# SCH-00001-AB-01.net
KiCad netlist of a schematic drawn in Altium Designer
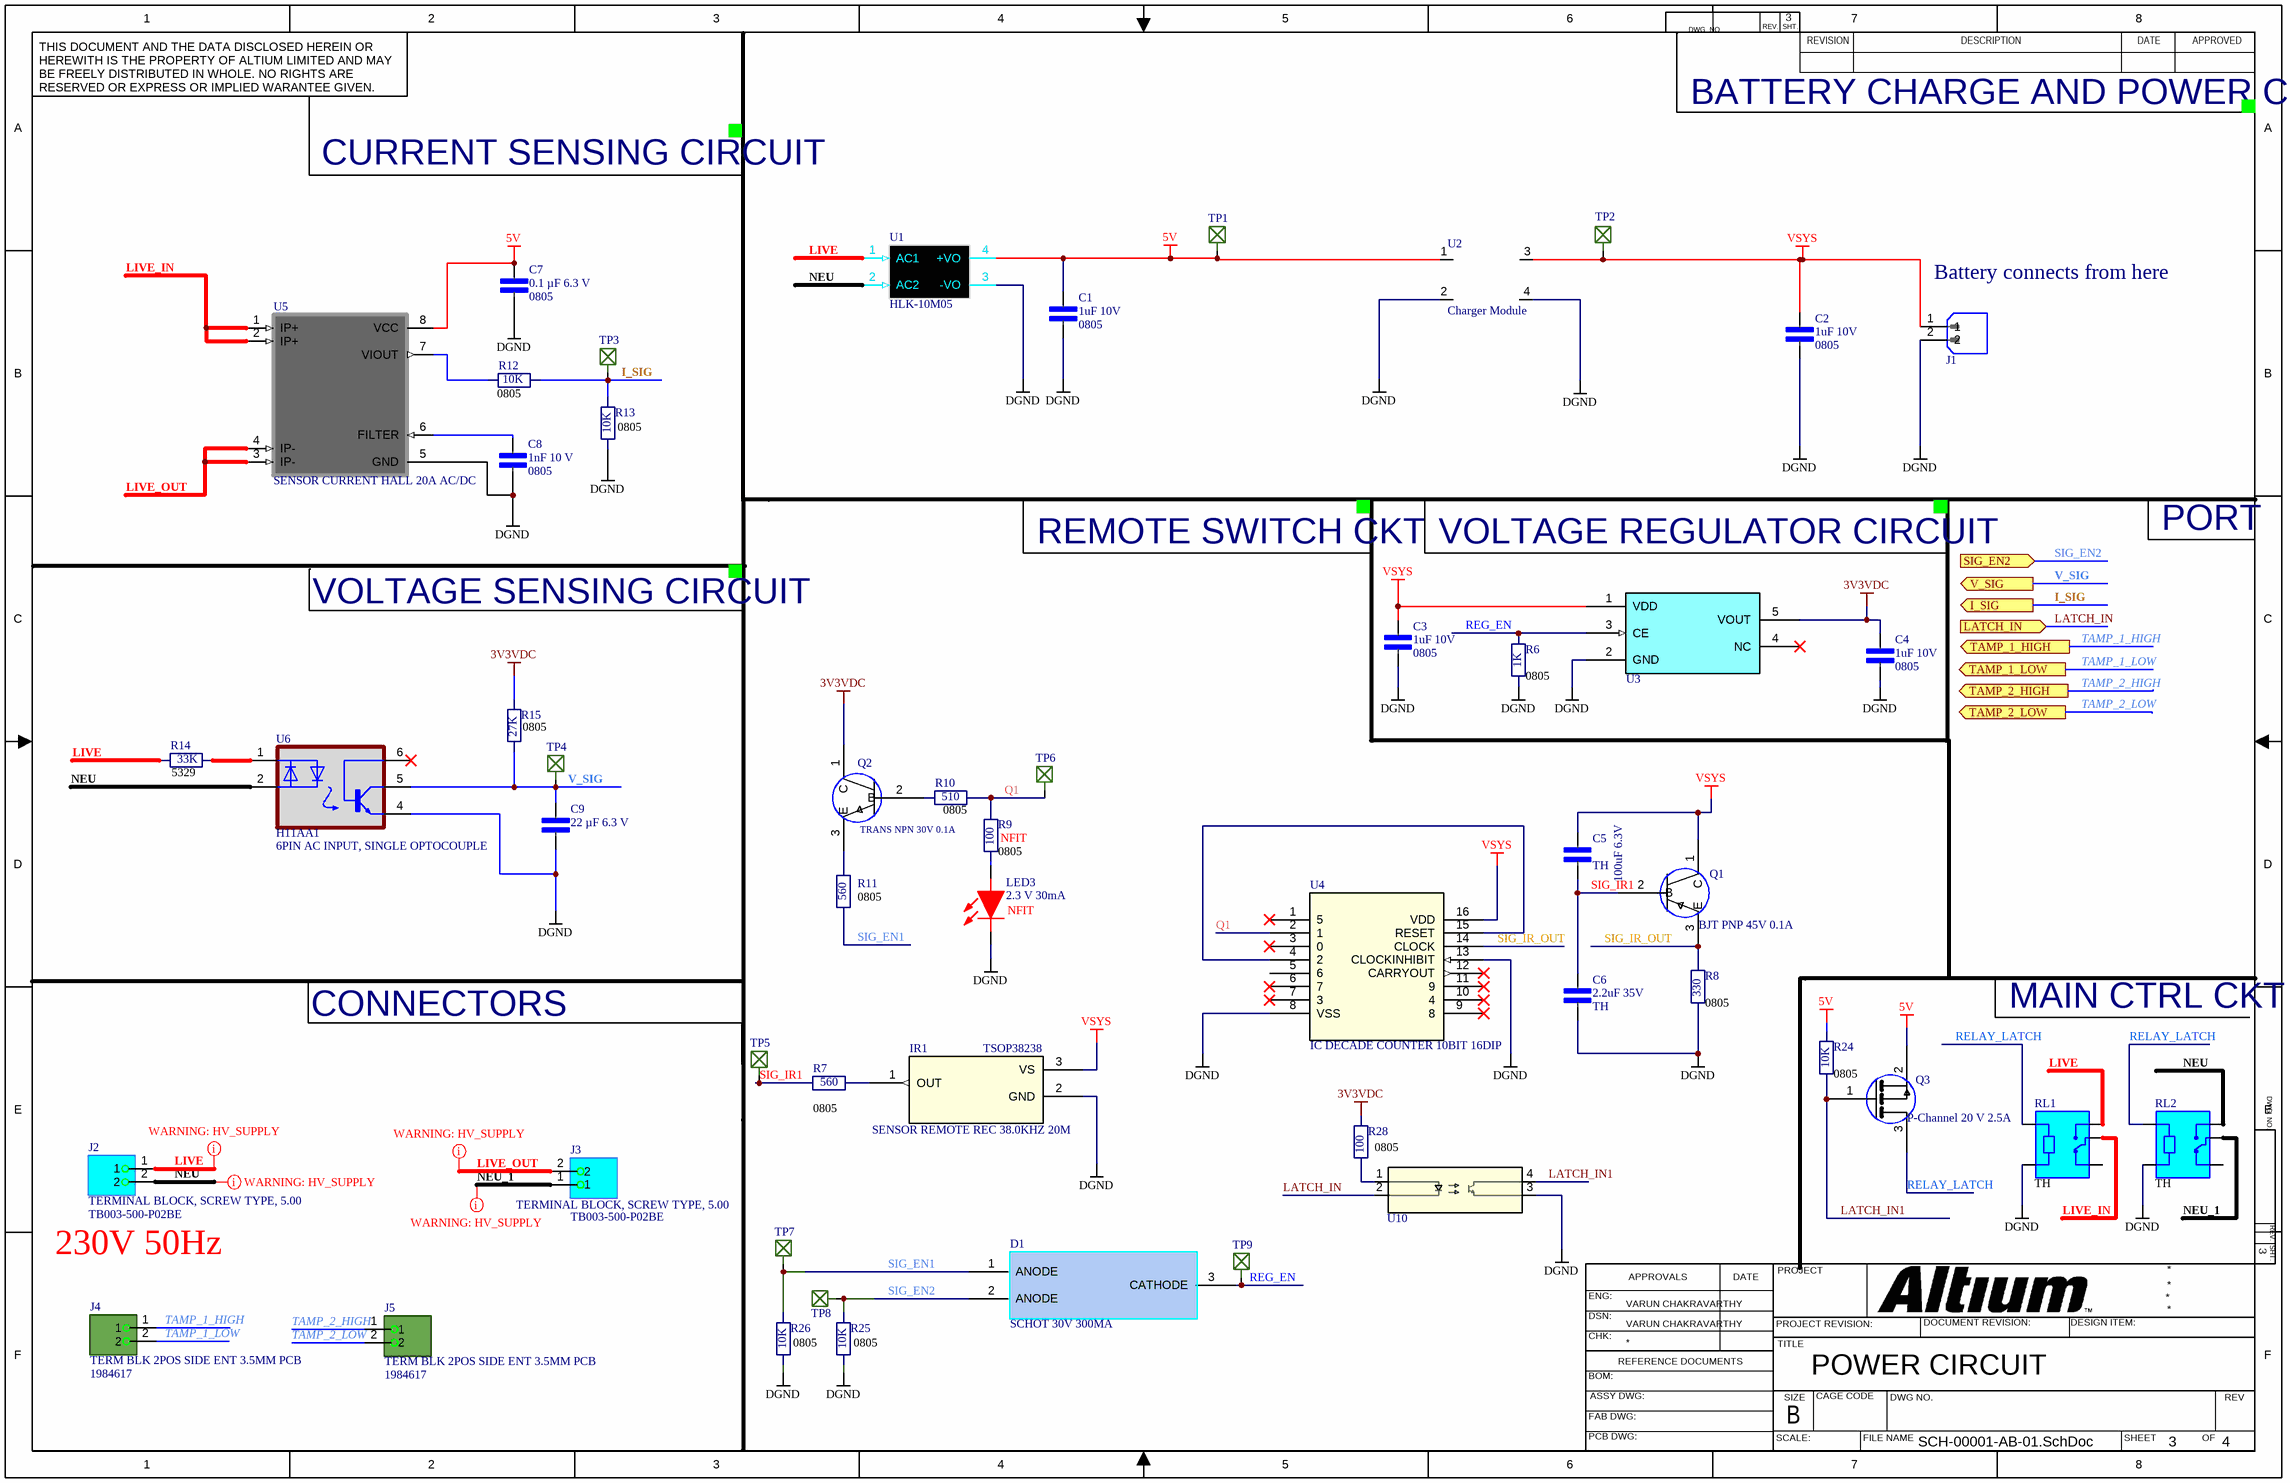
[diagram p0: SCH-00001-AB-01.SchDoc]

(export (version "E")
  (design (tool "Eeschema 10.0.6"))
  (components
    (comp (ref "C1")
      (value "1uF 10V")
      (footprint "CAP0805")
      (description "1 µF ±10% 10V Ceramic Capacitor X7R 0805 (2012 Metric)")
      (fields
        (field (name "MANUFACTURER") "Murata Electronics")
        (field (name "MANUFACTURER PART NO.") "GRM21BR71A105KA01L")
        (field (name "PACKAGE") "0805")
        (field (name "DATE DRAWN") "01/09/24")
        (field (name "DRAWN BY") "Varun Chakravarthy")
      )
      (libsource (lib "00001-A-01") (part "GRM21BR71A105KA01L"))
    )
    (comp (ref "C2")
      (value "1uF 10V")
      (footprint "CAP0805")
      (description "1 µF ±10% 10V Ceramic Capacitor X7R 0805 (2012 Metric)")
      (fields
        (field (name "MANUFACTURER") "Murata Electronics")
        (field (name "MANUFACTURER PART NO.") "GRM21BR71A105KA01L")
        (field (name "PACKAGE") "0805")
        (field (name "DATE DRAWN") "01/09/24")
        (field (name "DRAWN BY") "Varun Chakravarthy")
      )
      (libsource (lib "00001-A-01") (part "GRM21BR71A105KA01L"))
    )
    (comp (ref "C3")
      (value "1uF 10V")
      (footprint "CAP0805")
      (description "1 µF ±10% 10V Ceramic Capacitor X7R 0805 (2012 Metric)")
      (fields
        (field (name "MANUFACTURER") "Murata Electronics")
        (field (name "MANUFACTURER PART NO.") "GRM21BR71A105KA01L")
        (field (name "PACKAGE") "0805")
        (field (name "DATE DRAWN") "01/09/24")
        (field (name "DRAWN BY") "Varun Chakravarthy")
      )
      (libsource (lib "00001-A-01") (part "GRM21BR71A105KA01L"))
    )
    (comp (ref "C4")
      (value "1uF 10V")
      (footprint "CAP0805")
      (description "1 µF ±10% 10V Ceramic Capacitor X7R 0805 (2012 Metric)")
      (fields
        (field (name "MANUFACTURER") "Murata Electronics")
        (field (name "MANUFACTURER PART NO.") "GRM21BR71A105KA01L")
        (field (name "PACKAGE") "0805")
        (field (name "DATE DRAWN") "01/09/24")
        (field (name "DRAWN BY") "Varun Chakravarthy")
      )
      (libsource (lib "00001-A-01") (part "GRM21BR71A105KA01L"))
    )
    (comp (ref "C5")
      (value "100uF 6.3V")
      (footprint "EC-A_PAN")
      (description "100 µF 6.3 V Aluminum Electrolytic Capacitors Radial, Can 2000 Hrs @ 85°C")
      (fields
        (field (name "MANUFACTURER") "Panasonic Electronic Components")
        (field (name "MANUFACTURER PART NO.") "ECA-0JM101")
        (field (name "VALUE 2") "TH")
        (field (name "DATE DRAWN") "12/09/2024")
        (field (name "DRAWN BY") "Varun Chakravarthy")
      )
      (libsource (lib "00001-A-01") (part "ECA-0JM101"))
    )
    (comp (ref "C6")
      (value "2.2uF 35V")
      (footprint "CAP_RN_10X12P5_NCH")
      (description "2.2 µF 35 V Aluminum Electrolytic Capacitors Radial, Can 20000 Hrs @ 105°C")
      (fields
        (field (name "MANUFACTURER") "Nichicon")
        (field (name "MANUFACTURER PART NO.") "UPX1V2R2MPD")
        (field (name "VALUE 2") "TH")
        (field (name "DATE DRAWN") "12/09/2024")
        (field (name "DRAWN BY") "Varun Chakravarthy")
      )
      (libsource (lib "00001-A-01") (part "UPX1V2R2MPD"))
    )
    (comp (ref "C7")
      (value "0.1 µF 6.3 V")
      (footprint "CAP0805")
      (description "0.1 µF ±10% 6.3V Ceramic Capacitor X5R 0805 (2012 Metric)")
      (fields
        (field (name "MANUFACTURER") "KYOCERA AVX")
        (field (name "MANUFACTURER PART NO.") "08056D104KAT2A")
        (field (name "VALUE 2") "0805")
        (field (name "DATE DRAWN") "04/07/24")
        (field (name "DRAWN BY") "Varun Chakravarthy")
      )
      (libsource (lib "00001-A-01") (part "08056D104KAT2A"))
    )
    (comp (ref "C8")
      (value "1nF 10 V")
      (footprint "CAP0805")
      (description "1000 pF ±10% 10V Ceramic Capacitor X7R 0805 (2012 Metric)")
      (fields
        (field (name "MANUFACTURER") "KEMET")
        (field (name "MANUFACTURER PART NO.") "C0805C102K8RAC7800")
        (field (name "VALUE 2") "0805")
        (field (name "DATE DRAWN") "16/09/24")
        (field (name "DRAWN BY") "Varun Chakravarthy")
      )
      (libsource (lib "00001-A-01") (part "C0805C102K8RAC7800"))
    )
    (comp (ref "C9")
      (value "22 µF 6.3 V")
      (footprint "CAP0805")
      (description "22 µF ±10% 6.3V Ceramic Capacitor X5R 0805 (2012 Metric)")
      (fields
        (field (name "MANUFACTURER") "Samsung Electro-Mechanics")
        (field (name "MANUFACTURER PART NO.") "CL21A226KQCLRNC")
        (field (name "DATE DRAWN") "03/9/2024")
        (field (name "DRAWN BY") "Varun Chakravarthy")
      )
      (libsource (lib "00001-A-01") (part "CL21A226KQCLRNC"))
    )
    (comp (ref "D1")
      (value "SCHOT 30V 300MA")
      (footprint "SOT-323_2P2X1P35X1P3_STM-M")
      (description "Remote Receiver Sensor 38.0kHz 20m Through Hole")
      (fields
        (field (name "MANUFACTURER") "STMicroelectronics")
        (field (name "MANUFACTURER PART NO.") "BAT30CWFILM")
        (field (name "DATE DRAWN") "12/07/24")
        (field (name "DRAWN BY") "Varun Chakravarthy")
      )
      (libsource (lib "00001-A-01") (part "BAT30CWFILM"))
    )
    (comp (ref "IR1")
      (value "TSOP38238")
      (footprint "TSOP382")
      (description "Remote Receiver Sensor 38.0kHz 20m Through Hole")
      (fields
        (field (name "MANUFACTURER") "KYOCERA AVX")
        (field (name "DISTRIBUTOR 1 PART NO.") "751-1227-ND")
        (field (name "ALTIUM_VALUE") "SENSOR REMOTE REC 38.0KHZ 20M")
        (field (name "DATE DRAWN") "04/07/24")
        (field (name "DRAWN BY") "Varun Chakravarthy")
      )
      (libsource (lib "00001-A-01") (part "TSOP38238"))
    )
    (comp (ref "J1")
      (value "1053131102")
      (footprint "CON_1053131102")
      (description "Connector Header Through Hole, Right Angle 2 position 0.049\" (1.25mm)")
      (fields
        (field (name "MANUFACTURER") "Molex")
        (field (name "DISTRIBUTOR 1 PART NO.") "WM16893-ND")
        (field (name "DATE DRAWN") "6/10/24")
        (field (name "DRAWN BY") "Varun")
        (field (name "VERIFIED BY") "*")
      )
      (libsource (lib "00001-A-01") (part "1053131102"))
    )
    (comp (ref "J2")
      (value "TERMINAL BLOCK, SCREW TYPE, 5.00")
      (footprint "CUI_TB003-500-P02BE")
      (description "2 Position Wire to Board Terminal Block Horizontal with Board 0.197\" (5.00mm) Through Hole")
      (fields
        (field (name "MANUFACTURER") "Same Sky")
        (field (name "DISTRIBUTOR 1 PART NO.") "102-6161-ND")
        (field (name "MANUFACTURER PART NO.") "TB003-500-P02BE")
        (field (name "DATE DRAWN") "26/09/24")
        (field (name "DRAWN BY") "Varun Chakravarthy")
      )
      (libsource (lib "") (part "TB003-500-P02BE_1"))
    )
    (comp (ref "J3")
      (value "TERMINAL BLOCK, SCREW TYPE, 5.00")
      (footprint "CUI_TB003-500-P02BE")
      (description "2 Position Wire to Board Terminal Block Horizontal with Board 0.197\" (5.00mm) Through Hole")
      (fields
        (field (name "MANUFACTURER") "Same Sky")
        (field (name "DISTRIBUTOR 1 PART NO.") "102-6161-ND")
        (field (name "MANUFACTURER PART NO.") "TB003-500-P02BE")
        (field (name "DATE DRAWN") "26/09/24")
        (field (name "DRAWN BY") "Varun Chakravarthy")
      )
      (libsource (lib "00001-A-01") (part "TB003-500-P02BE"))
    )
    (comp (ref "J4")
      (value "TERM BLK 2POS SIDE ENT 3.5MM PCB")
      (footprint "PHOENIX_1984617")
      (description "2 Position Wire to Board Terminal Block Horizontal with Board 0.138\" (3.50mm) Through Hole")
      (fields
        (field (name "MANUFACTURER") "Phoenix Contact")
        (field (name "DISTRIBUTOR 1 PART NO.") "277-1721-ND")
        (field (name "MANUFACTURER PART NO.") "1984617")
        (field (name "DATE DRAWN") "17/09/24")
        (field (name "DRAWN BY") "Varun Chakravarthy")
      )
      (libsource (lib "00001-A-01") (part "1984617"))
    )
    (comp (ref "J5")
      (value "TERM BLK 2POS SIDE ENT 3.5MM PCB")
      (footprint "PHOENIX_1984617")
      (description "2 Position Wire to Board Terminal Block Horizontal with Board 0.138\" (3.50mm) Through Hole")
      (fields
        (field (name "MANUFACTURER") "Phoenix Contact")
        (field (name "DISTRIBUTOR 1 PART NO.") "277-1721-ND")
        (field (name "MANUFACTURER PART NO.") "1984617")
        (field (name "DATE DRAWN") "17/09/24")
        (field (name "DRAWN BY") "Varun Chakravarthy")
      )
      (libsource (lib "") (part "1984617_1"))
    )
    (comp (ref "LED3")
      (value "2.3 V 30mA")
      (footprint "LEDM2214X140N")
      (description "Standard LEDs - SMD Super Red, 633nm 224mcd, 20mA")
      (fields
        (field (name "MANUFACTURER") "ams OSRAM")
        (field (name "DISTRIBUTOR 1 PART NO.") "720-LSM676-Q2S1-1-Z")
        (field (name "FIT/NFIT") "NFIT")
        (field (name "DRAWN BY") "Varun")
        (field (name "DATE DRAWN") "12/072023")
        (field (name "VERIFIED BY") "*")
      )
      (libsource (lib "00001-A-01") (part "LS M676-Q2S1-1-Z"))
    )
    (comp (ref "Q1")
      (value "BJT PNP 45V 0.1A")
      (footprint "TO-92-3L_5P33X5P2_ONS")
      (description "P-Channel 20 V 2.5A (Ta) 800mW (Ta) Surface Mount SOT-23-3")
      (fields
        (field (name "MANUFACTURER") "onsemi")
        (field (name "MANUFACTURER PART NO.") "BC557ATA")
        (field (name "DATE DRAWN") "12/09/24")
        (field (name "DRAWN BY") "Varun Chakravarthy")
      )
      (libsource (lib "00001-A-01") (part "BC557"))
    )
    (comp (ref "Q2")
      (value "TRANS NPN 30V 0.1A")
      (footprint "TO-92-3L_5P33X5P2_ONS")
      (description "Bipolar (BJT) Transistor NPN 30 V 100 mA 300MHz 500 mW Through Hole TO-92-3")
      (fields
        (field (name "MANUFACTURER") "Fairchild Semiconductor")
        (field (name "MANUFACTURER PART NO.") "BC548")
        (field (name "DATE DRAWN") "12/09/24")
        (field (name "DRAWN BY") "Varun Chakravarthy")
      )
      (libsource (lib "00001-A-01") (part "BC548"))
    )
    (comp (ref "Q3")
      (value "P-Channel 20 V 2.5A")
      (footprint "SOT23_DMG2301U_DIO")
      (description "P-Channel 20 V 2.5A (Ta) 800mW (Ta) Surface Mount SOT-23-3")
      (fields
        (field (name "MANUFACTURER") "Diodes Incorporated")
        (field (name "MANUFACTURER PART NO.") "DMG2301U-7")
        (field (name "DATE DRAWN") "05/09/24")
        (field (name "DRAWN BY") "Varun Chakravarthy")
      )
      (libsource (lib "00001-A-01") (part "DMG2301U-7"))
    )
    (comp (ref "R6")
      (value "1K")
      (footprint "RES0805")
      (description "1 kOhms ±5% 0.125W, 1/8W Chip Resistor 0805 (2012 Metric) Automotive AEC-Q200 Thick Film")
      (fields
        (field (name "MANUFACTURER") "Panasonic Electronic Components")
        (field (name "MANUFACTURER PART NO.") "P1.0KACT-ND")
        (field (name "PACKAGE") "0805")
        (field (name "DATE DRAWN") "1/9/2024")
        (field (name "VERIFIED BY") "*")
      )
      (libsource (lib "00001-A-01") (part "ERJ-6GEYJ102V"))
    )
    (comp (ref "R7")
      (value "560")
      (footprint "RES0805")
      (description "560 Ohms ±0.1% 0.125W, 1/8W Chip Resistor 0805 (2012 Metric) Automotive AEC-Q200 Thin Film")
      (fields
        (field (name "MANUFACTURER") "Panasonic Electronic Components")
        (field (name "MANUFACTURER PART NO.") "ERA-6AEB561V")
        (field (name "PACKAGE") "0805")
        (field (name "DATE DRAWN") "12/9/2024")
        (field (name "VERIFIED BY") "*")
      )
      (libsource (lib "00001-A-01") (part "ERA-6AEB561V"))
    )
    (comp (ref "R8")
      (value "330")
      (footprint "RES0805")
      (description "330 Ohms ±0.1% 0.125W, 1/8W Chip Resistor 0805 (2012 Metric) Automotive AEC-Q200 Thin Film")
      (fields
        (field (name "MANUFACTURER") "Panasonic Electronic Components")
        (field (name "MANUFACTURER PART NO.") "ERA-6AEB331V")
        (field (name "PACKAGE") "0805")
        (field (name "DATE DRAWN") "12/9/2024")
        (field (name "VERIFIED BY") "*")
      )
      (libsource (lib "00001-A-01") (part "ERA-6AEB331V"))
    )
    (comp (ref "R9")
      (value "100")
      (footprint "RES0805")
      (description "100 Ohms ±0.1% 0.125W, 1/8W Chip Resistor 0805 (2012 Metric) Automotive AEC-Q200 Thin Film")
      (fields
        (field (name "MANUFACTURER") "Panasonic Electronic Components")
        (field (name "MANUFACTURER PART NO.") "ERA-6AEB101V")
        (field (name "FIT/NFIT") "NFIT")
        (field (name "PACKAGE") "0805")
        (field (name "DATE DRAWN") "12/9/2024")
        (field (name "VERIFIED BY") "*")
      )
      (libsource (lib "00001-A-01") (part "ERA-6AEB101V"))
    )
    (comp (ref "R10")
      (value "510")
      (footprint "RES0805")
      (description "510 Ohms ±0.1% 0.125W, 1/8W Chip Resistor 0805 (2012 Metric) Automotive AEC-Q200 Thin Film")
      (fields
        (field (name "MANUFACTURER") "Panasonic Electronic Components")
        (field (name "MANUFACTURER PART NO.") "ERA-6AEB511V")
        (field (name "PACKAGE") "0805")
        (field (name "DATE DRAWN") "12/9/2024")
        (field (name "VERIFIED BY") "*")
      )
      (libsource (lib "00001-A-01") (part "ERA-6AEB511V"))
    )
    (comp (ref "R11")
      (value "560")
      (footprint "RES0805")
      (description "560 Ohms ±0.1% 0.125W, 1/8W Chip Resistor 0805 (2012 Metric) Automotive AEC-Q200 Thin Film")
      (fields
        (field (name "MANUFACTURER") "Panasonic Electronic Components")
        (field (name "MANUFACTURER PART NO.") "ERA-6AEB561V")
        (field (name "PACKAGE") "0805")
        (field (name "DATE DRAWN") "12/9/2024")
        (field (name "VERIFIED BY") "*")
      )
      (libsource (lib "") (part "ERA-6AEB561V_1"))
    )
    (comp (ref "R12")
      (value "10K")
      (footprint "RES0805")
      (description "10 kOhms ±0.1% 0.125W, 1/8W Chip Resistor 0805 (2012 Metric) Automotive AEC-Q200 Thin Film")
      (fields
        (field (name "MANUFACTURER") "Panasonic Electronic Components")
        (field (name "MANUFACTURER PART NO.") "ERA-6AEB103V")
        (field (name "PACKAGE") "0805")
        (field (name "DATE DRAWN") "1/9/2024")
        (field (name "VERIFIED BY") "*")
      )
      (libsource (lib "") (part "ERA-6AEB103V_1"))
    )
    (comp (ref "R13")
      (value "10K")
      (footprint "RES0805")
      (description "10 kOhms ±0.1% 0.125W, 1/8W Chip Resistor 0805 (2012 Metric) Automotive AEC-Q200 Thin Film")
      (fields
        (field (name "MANUFACTURER") "Panasonic Electronic Components")
        (field (name "MANUFACTURER PART NO.") "ERA-6AEB103V")
        (field (name "PACKAGE") "0805")
        (field (name "DATE DRAWN") "1/9/2024")
        (field (name "VERIFIED BY") "*")
      )
      (libsource (lib "00001-A-01") (part "ERA-6AEB103V"))
    )
    (comp (ref "R14")
      (value "33K")
      (footprint "RES_SMF5_TYCO_TYC")
      (fields
        (field (name "MANUFACTURER") "TE Connectivity Passive Product")
        (field (name "MANUFACTURER PART NO.") "SMF533KJT")
        (field (name "DISTRIBUTOR 1 PART NO.") "A106035CT-ND")
        (field (name "PACKAGE") "5329")
        (field (name "DATE DRAWN") "17/9/2024")
        (field (name "VERIFIED BY") "*")
      )
      (libsource (lib "00001-A-01") (part "SMF533KJT"))
    )
    (comp (ref "R15")
      (value "27K")
      (footprint "RES0805")
      (description "27 kOhms ±5% 0.125W, 1/8W Chip Resistor 0805 (2012 Metric) Automotive AEC-Q200 Thick Film")
      (fields
        (field (name "MANUFACTURER") "Panasonic Electronic Components")
        (field (name "MANUFACTURER PART NO.") "ERJ-6GEYJ273V")
        (field (name "PACKAGE") "0805")
        (field (name "DATE DRAWN") "1/9/2024")
        (field (name "VERIFIED BY") "*")
      )
      (libsource (lib "00001-A-01") (part "ERJ-6GEYJ273V"))
    )
    (comp (ref "R24")
      (value "10K")
      (footprint "RES0805")
      (description "10 kOhms ±0.1% 0.125W, 1/8W Chip Resistor 0805 (2012 Metric) Automotive AEC-Q200 Thin Film")
      (fields
        (field (name "MANUFACTURER") "Panasonic Electronic Components")
        (field (name "MANUFACTURER PART NO.") "ERA-6AEB103V")
        (field (name "PACKAGE") "0805")
        (field (name "DATE DRAWN") "1/9/2024")
        (field (name "VERIFIED BY") "*")
      )
      (libsource (lib "00001-A-01") (part "ERA-6AEB103V"))
    )
    (comp (ref "R25")
      (value "10K")
      (footprint "RES0805")
      (description "10 kOhms ±0.1% 0.125W, 1/8W Chip Resistor 0805 (2012 Metric) Automotive AEC-Q200 Thin Film")
      (fields
        (field (name "MANUFACTURER") "Panasonic Electronic Components")
        (field (name "MANUFACTURER PART NO.") "ERA-6AEB103V")
        (field (name "PACKAGE") "0805")
        (field (name "DATE DRAWN") "1/9/2024")
        (field (name "VERIFIED BY") "*")
      )
      (libsource (lib "00001-A-01") (part "ERA-6AEB103V"))
    )
    (comp (ref "R26")
      (value "10K")
      (footprint "RES0805")
      (description "10 kOhms ±0.1% 0.125W, 1/8W Chip Resistor 0805 (2012 Metric) Automotive AEC-Q200 Thin Film")
      (fields
        (field (name "MANUFACTURER") "Panasonic Electronic Components")
        (field (name "MANUFACTURER PART NO.") "ERA-6AEB103V")
        (field (name "PACKAGE") "0805")
        (field (name "DATE DRAWN") "1/9/2024")
        (field (name "VERIFIED BY") "*")
      )
      (libsource (lib "00001-A-01") (part "ERA-6AEB103V"))
    )
    (comp (ref "R28")
      (value "100")
      (footprint "RES0805")
      (description "100 Ohms ±5% 0.125W, 1/8W Chip Resistor 0805 (2012 Metric) Automotive AEC-Q200 Thick Film")
      (fields
        (field (name "MANUFACTURER") "Panasonic Electronic Components")
        (field (name "MANUFACTURER PART NO.") "ERJ-6GEYJ101V")
        (field (name "PACKAGE") "0805")
        (field (name "DATE DRAWN") "1/9/2024")
        (field (name "VERIFIED BY") "*")
      )
      (libsource (lib "00001-A-01") (part "ERJ-6GEYJ101V"))
    )
    (comp (ref "RL1")
      (value "SRD-05VDC-SL-C")
      (footprint "RELAY_SRD-05VDC-SL-C")
      (description "5V Trigger Relay Module")
      (fields
        (field (name "MANUFACTURER") "SongLe")
        (field (name "DISTRIBUTOR 1 PART NO.") "340142-SRD-05VDC-SL-C")
        (field (name "PACKAGE") "TH")
        (field (name "DATE DRAWN") "12/9/2024")
        (field (name "VERIFIED BY") "*")
      )
      (libsource (lib "00001-A-01") (part "SRD-05VDC-SL-C"))
    )
    (comp (ref "RL2")
      (value "SRD-05VDC-SL-C")
      (footprint "RELAY_SRD-05VDC-SL-C")
      (description "5V Trigger Relay Module")
      (fields
        (field (name "MANUFACTURER") "SongLe")
        (field (name "DISTRIBUTOR 1 PART NO.") "340142-SRD-05VDC-SL-C")
        (field (name "PACKAGE") "TH")
        (field (name "DATE DRAWN") "12/9/2024")
        (field (name "VERIFIED BY") "*")
      )
      (libsource (lib "00001-A-01") (part "SRD-05VDC-SL-C"))
    )
    (comp (ref "TP1")
      (value "TEST point")
      (footprint "TEST_POINT")
      (libsource (lib "00001-A-01") (part "TP"))
    )
    (comp (ref "TP2")
      (value "TEST point")
      (footprint "TEST_POINT")
      (libsource (lib "00001-A-01") (part "TP"))
    )
    (comp (ref "TP3")
      (value "TEST point")
      (footprint "TEST_POINT")
      (libsource (lib "00001-A-01") (part "TP"))
    )
    (comp (ref "TP4")
      (value "TEST point")
      (footprint "TEST_POINT")
      (libsource (lib "00001-A-01") (part "TP"))
    )
    (comp (ref "TP5")
      (value "TEST point")
      (footprint "TEST_POINT")
      (libsource (lib "00001-A-01") (part "TP"))
    )
    (comp (ref "TP6")
      (value "TEST point")
      (footprint "TEST_POINT")
      (libsource (lib "00001-A-01") (part "TP"))
    )
    (comp (ref "TP7")
      (value "TEST point")
      (footprint "TEST_POINT")
      (libsource (lib "00001-A-01") (part "TP"))
    )
    (comp (ref "TP8")
      (value "TEST point")
      (footprint "TEST_POINT")
      (libsource (lib "00001-A-01") (part "TP"))
    )
    (comp (ref "TP9")
      (value "TEST point")
      (footprint "TEST_POINT")
      (libsource (lib "00001-A-01") (part "TP"))
    )
    (comp (ref "U1")
      (value "HLK-10M05")
      (footprint "CONV_HLK-10M05")
      (description "AC to DC Power Supply Module")
      (fields
        (field (name "MANUFACTURER") "Hi-link")
        (field (name "DISTRIBUTOR 1 PART NO.") "EC-4693")
        (field (name "MANUFACTURER PART NO.") "HLK-10M05")
        (field (name "DATE DRAWN") "31/8/24")
        (field (name "DRAWN BY") "Varun")
        (field (name "VERIFIED BY") "*")
      )
      (libsource (lib "00001-A-01") (part "HLK-10M05"))
    )
    (comp (ref "U2")
      (value "Charger Module")
      (footprint "TP5100_MODULE")
      (description "4.2v and 8.4v Dual One/Two Battery Protection Board")
      (fields
        (field (name "MANUFACTURER") "Tap ower ASIC")
        (field (name "MANUFACTURER PART NO.") "TP5100")
        (field (name "DATE DRAWN") "10/07/24")
        (field (name "DRAWN BY") "Varun Chakravarthy")
      )
      (libsource (lib "00001-A-01") (part "TP5100"))
    )
    (comp (ref "U3")
      (value "RP170N331D-TR-FE")
      (footprint "SOT-23-5SC-74A_PE-SOT-23-5-180326_NMD-M")
      (description "Linear Voltage Regulator IC Positive Fixed 1 Output 300mA SOT-23-5")
      (fields
        (field (name "MANUFACTURER") "Nisshinbo Micro Devices Inc.")
        (field (name "DISTRIBUTOR 1 PART NO.") "2129-RP170N331D-TR-FECT-ND")
        (field (name "DATE DRAWN") "31/8/24")
        (field (name "DRAWN BY") "Varun")
        (field (name "VERIFIED BY") "*")
      )
      (libsource (lib "00001-A-01") (part "RP170N331D-TR-FE"))
    )
    (comp (ref "U4")
      (value "IC DECADE COUNTER 10BIT 16DIP")
      (footprint "DIP794W45P254L1969H508Q16")
      (description "Counter IC Counter, Decade 1 Element 10 Bit Positive, Negative 16-PDIP")
      (fields
        (field (name "MANUFACTURER") "Texas Instruments")
        (field (name "MANUFACTURER PART NO.") "CD4017BE")
        (field (name "DATE DRAWN") "08/09/24")
        (field (name "DRAWN BY") "Varun Chakravarthy")
      )
      (libsource (lib "00001-A-01") (part "CD4017BE"))
    )
    (comp (ref "U5")
      (value "SENSOR CURRENT HALL 20A AC/DC")
      (footprint "SOIC127P600X175-8N")
      (description "Current Sensor 20A 1 Channel Hall Effect, Open Loop Bidirectional 8-SOIC (0.154\", 3.90mm Width)")
      (fields
        (field (name "MANUFACTURER") "onsemi")
        (field (name "MANUFACTURER PART NO.") "ACS712ELCTR-20A-T")
        (field (name "DATE DRAWN") "16/09/24")
        (field (name "DRAWN BY") "Varun Chakravarthy")
      )
      (libsource (lib "00001-A-01") (part "ACS712ELCTR-20A-T"))
    )
    (comp (ref "U6")
      (value "6PIN AC INPUT, SINGLE OPTOCOUPLE")
      (footprint "DIP762W50P254L730H410Q6")
      (description "Optoisolator Transistor with Base Output 5000Vrms 1 Channel 6-DIP")
      (fields
        (field (name "MANUFACTURER") "Isocom Components 2004 LTD")
        (field (name "MANUFACTURER PART NO.") "H11AA1")
        (field (name "DISTRIBUTOR 1 PART NO.") "58-H11AA1-ND")
        (field (name "DATE DRAWN") "16/09/24")
        (field (name "DRAWN BY") "Varun Chakravarthy")
      )
      (libsource (lib "00001-A-01") (part "H11AA1"))
    )
    (comp (ref "U10")
      (value "PC81710NIP1B")
      (footprint "SOP_PC8171_SCT-M")
      (description "Optoisolator Transistor Output 5000Vrms 1 Channel 4-SMD")
      (fields
        (field (name "MANUFACTURER") "SHARP/Socle Technology")
        (field (name "DISTRIBUTOR 1 PART NO.") "1855-1014-1-ND")
        (field (name "DATE DRAWN") "05/07/24")
        (field (name "VERIFIED BY") "*")
      )
      (libsource (lib "00001-A-01") (part "PC81710NIP1B"))
    )
  )
  (nets
    (net (code "1") (name "/I_SIG") (class "Default")
      (node (ref "R12") (pin "2") (pinfunction "2_2") (pintype "passive"))
      (node (ref "R13") (pin "2") (pinfunction "2_2") (pintype "passive"))
      (node (ref "TP3") (pin "1") (pinfunction "G_1") (pintype "passive"))
    )
    (net (code "2") (name "/LATCH_IN") (class "Default")
      (node (ref "U10") (pin "2") (pinfunction "CATHODE_2") (pintype "passive"))
    )
    (net (code "3") (name "/LATCH_IN1") (class "Default")
      (node (ref "Q3") (pin "1") (pinfunction "1/G_1") (pintype "passive"))
      (node (ref "R24") (pin "1") (pinfunction "1_1") (pintype "passive"))
      (node (ref "U10") (pin "4") (pinfunction "COLLECTOR_4") (pintype "passive"))
    )
    (net (code "4") (name "/LIVE") (class "Default")
      (node (ref "J2") (pin "1") (pinfunction "1_1") (pintype "passive"))
      (node (ref "R14") (pin "1") (pinfunction "1_1") (pintype "passive"))
      (node (ref "RL1") (pin "NO") (pinfunction "NO_NO") (pintype "passive"))
      (node (ref "U1") (pin "1") (pinfunction "AC1_1") (pintype "input"))
    )
    (net (code "5") (name "/LIVE_IN") (class "Default")
      (node (ref "RL1") (pin "COM") (pinfunction "COM_COM") (pintype "passive"))
      (node (ref "U5") (pin "1") (pinfunction "IP+_1") (pintype "input"))
      (node (ref "U5") (pin "2") (pinfunction "IP+_2") (pintype "input"))
    )
    (net (code "6") (name "/LIVE_OUT") (class "Default")
      (node (ref "J3") (pin "2") (pinfunction "2_2") (pintype "passive"))
      (node (ref "U5") (pin "3") (pinfunction "IP-_3") (pintype "input"))
      (node (ref "U5") (pin "4") (pinfunction "IP-_4") (pintype "input"))
    )
    (net (code "7") (name "/NEU") (class "Default")
      (node (ref "J2") (pin "2") (pinfunction "2_2") (pintype "passive"))
      (node (ref "RL2") (pin "NO") (pinfunction "NO_NO") (pintype "passive"))
      (node (ref "U1") (pin "2") (pinfunction "AC2_2") (pintype "input"))
      (node (ref "U6") (pin "2") (pinfunction "C/A_2") (pintype "passive"))
    )
    (net (code "8") (name "/NEU_1") (class "Default")
      (node (ref "J3") (pin "1") (pinfunction "1_1") (pintype "passive"))
      (node (ref "RL2") (pin "COM") (pinfunction "COM_COM") (pintype "passive"))
    )
    (net (code "9") (name "/Q1") (class "Default")
      (node (ref "R10") (pin "2") (pinfunction "2_2") (pintype "passive"))
      (node (ref "R9") (pin "2") (pinfunction "2_2") (pintype "passive"))
      (node (ref "TP6") (pin "1") (pinfunction "G_1") (pintype "passive"))
      (node (ref "U4") (pin "2") (pinfunction "1_2") (pintype "passive"))
    )
    (net (code "10") (name "/REG_EN") (class "Default")
      (node (ref "D1") (pin "3") (pinfunction "CATHODE_3") (pintype "passive"))
      (node (ref "R6") (pin "1") (pinfunction "1_1") (pintype "passive"))
      (node (ref "TP9") (pin "1") (pinfunction "G_1") (pintype "passive"))
      (node (ref "U3") (pin "3") (pinfunction "CE_3") (pintype "input"))
    )
    (net (code "11") (name "/RELAY_LATCH") (class "Default")
      (node (ref "Q3") (pin "3") (pinfunction "3/D_3") (pintype "passive"))
      (node (ref "RL1") (pin "A1") (pinfunction "A1_A1") (pintype "passive"))
      (node (ref "RL2") (pin "A1") (pinfunction "A1_A1") (pintype "passive"))
    )
    (net (code "12") (name "/SIG_EN1") (class "Default")
      (node (ref "D1") (pin "1") (pinfunction "ANODE_1") (pintype "passive"))
      (node (ref "R11") (pin "1") (pinfunction "1_1") (pintype "passive"))
      (node (ref "R26") (pin "2") (pinfunction "2_2") (pintype "passive"))
      (node (ref "TP7") (pin "1") (pinfunction "G_1") (pintype "passive"))
    )
    (net (code "13") (name "/SIG_EN2") (class "Default")
      (node (ref "D1") (pin "2") (pinfunction "ANODE_2") (pintype "passive"))
      (node (ref "R25") (pin "2") (pinfunction "2_2") (pintype "passive"))
      (node (ref "TP8") (pin "1") (pinfunction "G_1") (pintype "passive"))
    )
    (net (code "14") (name "/SIG_IR1") (class "Default")
      (node (ref "C5") (pin "2") (pinfunction "-_2") (pintype "passive"))
      (node (ref "C6") (pin "1") (pinfunction "+_1") (pintype "passive"))
      (node (ref "Q1") (pin "2") (pinfunction "B_2") (pintype "passive"))
      (node (ref "R7") (pin "1") (pinfunction "1_1") (pintype "passive"))
      (node (ref "TP5") (pin "1") (pinfunction "G_1") (pintype "passive"))
    )
    (net (code "15") (name "/SIG_IR_OUT") (class "Default")
      (node (ref "Q1") (pin "3") (pinfunction "E_3") (pintype "passive"))
      (node (ref "R8") (pin "2") (pinfunction "2_2") (pintype "passive"))
      (node (ref "U4") (pin "14") (pinfunction "CLOCK_14") (pintype "passive"))
    )
    (net (code "16") (name "/TAMP_1_HIGH") (class "Default")
      (node (ref "J4") (pin "1") (pinfunction "1_1") (pintype "passive"))
    )
    (net (code "17") (name "/TAMP_1_LOW") (class "Default")
      (node (ref "J4") (pin "2") (pinfunction "2_2") (pintype "passive"))
    )
    (net (code "18") (name "/TAMP_2_HIGH") (class "Default")
      (node (ref "J5") (pin "1") (pinfunction "1_1") (pintype "passive"))
    )
    (net (code "19") (name "/TAMP_2_LOW") (class "Default")
      (node (ref "J5") (pin "2") (pinfunction "2_2") (pintype "passive"))
    )
    (net (code "20") (name "/V_SIG") (class "Default")
      (node (ref "C9") (pin "1") (pinfunction "+_1") (pintype "passive"))
      (node (ref "R15") (pin "1") (pinfunction "1_1") (pintype "passive"))
      (node (ref "TP4") (pin "1") (pinfunction "G_1") (pintype "passive"))
      (node (ref "U6") (pin "5") (pinfunction "C_5") (pintype "passive"))
    )
    (net (code "21") (name "3V3VDC") (class "Default")
      (node (ref "C4") (pin "1") (pinfunction "+_1") (pintype "passive"))
      (node (ref "Q2") (pin "1") (pinfunction "C_1") (pintype "passive"))
      (node (ref "R15") (pin "2") (pinfunction "2_2") (pintype "passive"))
      (node (ref "R28") (pin "2") (pinfunction "2_2") (pintype "passive"))
      (node (ref "U3") (pin "5") (pinfunction "VOUT_5") (pintype "power_in"))
    )
    (net (code "22") (name "5V") (class "Default")
      (node (ref "C1") (pin "1") (pinfunction "+_1") (pintype "passive"))
      (node (ref "C7") (pin "1") (pinfunction "+_1") (pintype "passive"))
      (node (ref "Q3") (pin "2") (pinfunction "2/S_2") (pintype "passive"))
      (node (ref "R24") (pin "2") (pinfunction "2_2") (pintype "passive"))
      (node (ref "TP1") (pin "1") (pinfunction "G_1") (pintype "passive"))
      (node (ref "U1") (pin "4") (pinfunction "+VO_4") (pintype "passive"))
      (node (ref "U2") (pin "1") (pinfunction "NO_1") (pintype "passive"))
      (node (ref "U5") (pin "8") (pinfunction "VCC_8") (pintype "power_in"))
    )
    (net (code "23") (name "DGND") (class "Default")
      (node (ref "C1") (pin "2") (pinfunction "-_2") (pintype "passive"))
      (node (ref "C2") (pin "2") (pinfunction "-_2") (pintype "passive"))
      (node (ref "C3") (pin "2") (pinfunction "-_2") (pintype "passive"))
      (node (ref "C4") (pin "2") (pinfunction "-_2") (pintype "passive"))
      (node (ref "C6") (pin "2") (pinfunction "-_2") (pintype "passive"))
      (node (ref "C7") (pin "2") (pinfunction "-_2") (pintype "passive"))
      (node (ref "C8") (pin "2") (pinfunction "-_2") (pintype "passive"))
      (node (ref "C9") (pin "2") (pinfunction "-_2") (pintype "passive"))
      (node (ref "IR1") (pin "2") (pinfunction "GND_2") (pintype "power_in"))
      (node (ref "J1") (pin "2") (pinfunction "2_2") (pintype "passive"))
      (node (ref "LED3") (pin "1") (pinfunction "K_1") (pintype "passive"))
      (node (ref "R13") (pin "1") (pinfunction "1_1") (pintype "passive"))
      (node (ref "R25") (pin "1") (pinfunction "1_1") (pintype "passive"))
      (node (ref "R26") (pin "1") (pinfunction "1_1") (pintype "passive"))
      (node (ref "R6") (pin "2") (pinfunction "2_2") (pintype "passive"))
      (node (ref "R8") (pin "1") (pinfunction "1_1") (pintype "passive"))
      (node (ref "RL1") (pin "A2") (pinfunction "A2_A2") (pintype "passive"))
      (node (ref "RL2") (pin "A2") (pinfunction "A2_A2") (pintype "passive"))
      (node (ref "U1") (pin "3") (pinfunction "-VO_3") (pintype "passive"))
      (node (ref "U10") (pin "3") (pinfunction "EMITTER_3") (pintype "passive"))
      (node (ref "U2") (pin "2") (pinfunction "COM_2") (pintype "passive"))
      (node (ref "U2") (pin "4") (pinfunction "COM_4") (pintype "passive"))
      (node (ref "U3") (pin "2") (pinfunction "GND_2") (pintype "power_in"))
      (node (ref "U4") (pin "13") (pinfunction "CLOCKINHIBIT_13") (pintype "input"))
      (node (ref "U4") (pin "8") (pinfunction "VSS_8") (pintype "power_in"))
      (node (ref "U5") (pin "5") (pinfunction "GND_5") (pintype "power_in"))
      (node (ref "U6") (pin "4") (pinfunction "E_4") (pintype "passive"))
    )
    (net (code "24") (name "Net-(C8-+)") (class "Default")
      (node (ref "C8") (pin "1") (pinfunction "+_1") (pintype "passive"))
      (node (ref "U5") (pin "6") (pinfunction "FILTER_6") (pintype "input"))
    )
    (net (code "25") (name "Net-(IR1-OUT)") (class "Default")
      (node (ref "IR1") (pin "1") (pinfunction "OUT_1") (pintype "output"))
      (node (ref "R7") (pin "2") (pinfunction "2_2") (pintype "passive"))
    )
    (net (code "26") (name "Net-(LED3-A)") (class "Default")
      (node (ref "LED3") (pin "2") (pinfunction "A_2") (pintype "passive"))
      (node (ref "R9") (pin "1") (pinfunction "1_1") (pintype "passive"))
    )
    (net (code "27") (name "Net-(Q2-B)") (class "Default")
      (node (ref "Q2") (pin "2") (pinfunction "B_2") (pintype "passive"))
      (node (ref "R10") (pin "1") (pinfunction "1_1") (pintype "passive"))
    )
    (net (code "28") (name "Net-(Q2-E)") (class "Default")
      (node (ref "Q2") (pin "3") (pinfunction "E_3") (pintype "passive"))
      (node (ref "R11") (pin "2") (pinfunction "2_2") (pintype "passive"))
    )
    (net (code "29") (name "Net-(U4-2)") (class "Default")
      (node (ref "U4") (pin "15") (pinfunction "RESET_15") (pintype "passive"))
      (node (ref "U4") (pin "4") (pinfunction "2_4") (pintype "passive"))
    )
    (net (code "30") (name "Net-(U5-VIOUT)") (class "Default")
      (node (ref "R12") (pin "1") (pinfunction "1_1") (pintype "passive"))
      (node (ref "U5") (pin "7") (pinfunction "VIOUT_7") (pintype "output"))
    )
    (net (code "31") (name "Net-(U6-A{slash}C)") (class "Default")
      (node (ref "R14") (pin "2") (pinfunction "2_2") (pintype "passive"))
      (node (ref "U6") (pin "1") (pinfunction "A/C_1") (pintype "passive"))
    )
    (net (code "32") (name "Net-(U10-ANODE)") (class "Default")
      (node (ref "R28") (pin "1") (pinfunction "1_1") (pintype "passive"))
      (node (ref "U10") (pin "1") (pinfunction "ANODE_1") (pintype "passive"))
    )
    (net (code "33") (name "VSYS") (class "Default")
      (node (ref "C2") (pin "1") (pinfunction "+_1") (pintype "passive"))
      (node (ref "C3") (pin "1") (pinfunction "+_1") (pintype "passive"))
      (node (ref "C5") (pin "1") (pinfunction "+_1") (pintype "passive"))
      (node (ref "IR1") (pin "3") (pinfunction "VS_3") (pintype "passive"))
      (node (ref "J1") (pin "1") (pinfunction "1_1") (pintype "passive"))
      (node (ref "Q1") (pin "1") (pinfunction "C_1") (pintype "passive"))
      (node (ref "TP2") (pin "1") (pinfunction "G_1") (pintype "passive"))
      (node (ref "U2") (pin "3") (pinfunction "NO_3") (pintype "passive"))
      (node (ref "U3") (pin "1") (pinfunction "VDD_1") (pintype "power_in"))
      (node (ref "U4") (pin "16") (pinfunction "VDD_16") (pintype "power_in"))
    )
    (net (code "34") (name "unconnected-(RL1-PadNC)") (class "Default")
      (node (ref "RL1") (pin "NC") (pinfunction "NC_NC") (pintype "passive"))
    )
    (net (code "35") (name "unconnected-(RL2-PadNC)") (class "Default")
      (node (ref "RL2") (pin "NC") (pinfunction "NC_NC") (pintype "passive"))
    )
    (net (code "36") (name "unconnected-(U3-NC-Pad4)") (class "Default")
      (node (ref "U3") (pin "4") (pinfunction "NC_4") (pintype "passive+no_connect"))
    )
    (net (code "37") (name "unconnected-(U4-0-Pad3)") (class "Default")
      (node (ref "U4") (pin "3") (pinfunction "0_3") (pintype "passive+no_connect"))
    )
    (net (code "38") (name "unconnected-(U4-3-Pad7)") (class "Default")
      (node (ref "U4") (pin "7") (pinfunction "3_7") (pintype "passive+no_connect"))
    )
    (net (code "39") (name "unconnected-(U4-4-Pad10)") (class "Default")
      (node (ref "U4") (pin "10") (pinfunction "4_10") (pintype "passive+no_connect"))
    )
    (net (code "40") (name "unconnected-(U4-5-Pad1)") (class "Default")
      (node (ref "U4") (pin "1") (pinfunction "5_1") (pintype "passive+no_connect"))
    )
    (net (code "41") (name "unconnected-(U4-6-Pad5)") (class "Default")
      (node (ref "U4") (pin "5") (pinfunction "6_5") (pintype "passive"))
    )
    (net (code "42") (name "unconnected-(U4-7-Pad6)") (class "Default")
      (node (ref "U4") (pin "6") (pinfunction "7_6") (pintype "passive+no_connect"))
    )
    (net (code "43") (name "unconnected-(U4-8-Pad9)") (class "Default")
      (node (ref "U4") (pin "9") (pinfunction "8_9") (pintype "passive+no_connect"))
    )
    (net (code "44") (name "unconnected-(U4-9-Pad11)") (class "Default")
      (node (ref "U4") (pin "11") (pinfunction "9_11") (pintype "passive+no_connect"))
    )
    (net (code "45") (name "unconnected-(U4-CARRYOUT-Pad12)") (class "Default")
      (node (ref "U4") (pin "12") (pinfunction "CARRYOUT_12") (pintype "output+no_connect"))
    )
    (net (code "46") (name "unconnected-(U6-B-Pad6)") (class "Default")
      (node (ref "U6") (pin "6") (pinfunction "B_6") (pintype "passive+no_connect"))
    )
  )
)
